# Step-to-TalkV2.net
KiCad netlist of a schematic drawn in EAGLE
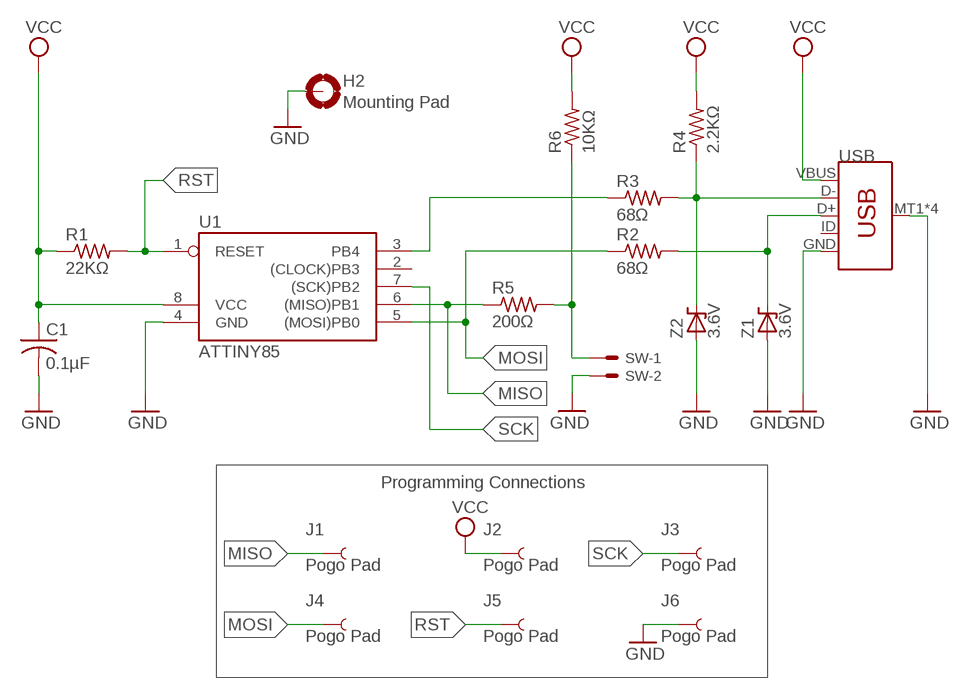
[diagram p0: schematic, sheet 1]

(export (version "E")
  (design (tool "Eeschema 10.0.6"))
  (components
    (comp (ref "C1")
      (value "0.1µF")
      (footprint "eagle-import:C0603")
      (libsource (lib "eagle-import") (part "C-USC0603"))
    )
    (comp (ref "H2")
      (value "Mounting Pad")
      (footprint "eagle-import:4,3-PAD")
      (libsource (lib "eagle-import") (part "MOUNT-PAD-ROUND4.3"))
    )
    (comp (ref "J1")
      (value "Pogo Pad")
      (footprint "eagle-import:PAD.03X.03")
      (libsource (lib "eagle-import") (part "TEST-POINT3"))
    )
    (comp (ref "J2")
      (value "Pogo Pad")
      (footprint "eagle-import:PAD.03X.03")
      (libsource (lib "eagle-import") (part "TEST-POINT3"))
    )
    (comp (ref "J3")
      (value "Pogo Pad")
      (footprint "eagle-import:PAD.03X.03")
      (libsource (lib "eagle-import") (part "TEST-POINT3"))
    )
    (comp (ref "J4")
      (value "Pogo Pad")
      (footprint "eagle-import:PAD.03X.03")
      (libsource (lib "eagle-import") (part "TEST-POINT3"))
    )
    (comp (ref "J5")
      (value "Pogo Pad")
      (footprint "eagle-import:PAD.03X.03")
      (libsource (lib "eagle-import") (part "TEST-POINT3"))
    )
    (comp (ref "J6")
      (value "Pogo Pad")
      (footprint "eagle-import:PAD.03X.03")
      (libsource (lib "eagle-import") (part "TEST-POINT3"))
    )
    (comp (ref "R1")
      (value "22KΩ")
      (footprint "eagle-import:R0603")
      (libsource (lib "eagle-import") (part "R-US_R0603"))
    )
    (comp (ref "R2")
      (value "68Ω")
      (footprint "eagle-import:R0603")
      (libsource (lib "eagle-import") (part "R-US_R0603"))
    )
    (comp (ref "R3")
      (value "68Ω")
      (footprint "eagle-import:R0603")
      (libsource (lib "eagle-import") (part "R-US_R0603"))
    )
    (comp (ref "R4")
      (value "2.2KΩ")
      (footprint "eagle-import:R0603")
      (libsource (lib "eagle-import") (part "R-US_R0603"))
    )
    (comp (ref "R5")
      (value "200Ω")
      (footprint "eagle-import:R0603")
      (libsource (lib "eagle-import") (part "R-US_R0603"))
    )
    (comp (ref "R6")
      (value "10KΩ")
      (footprint "eagle-import:R0603")
      (libsource (lib "eagle-import") (part "R-US_R0603"))
    )
    (comp (ref "SW")
      (value "87438-02")
      (footprint "eagle-import:87438-02")
      (libsource (lib "eagle-import") (part "87438-02"))
    )
    (comp (ref "U1")
      (value "ATTINY85")
      (footprint "eagle-import:SOIC8")
      (libsource (lib "eagle-import") (part "TINY22S"))
    )
    (comp (ref "USB")
      (value "USB_MICRO-B_SMT")
      (footprint "eagle-import:USB-MICROB")
      (libsource (lib "eagle-import") (part "USB_MICRO-B_SMT"))
    )
    (comp (ref "Z1")
      (value "3.6V")
      (footprint "eagle-import:SOD523-ENLARGED")
      (libsource (lib "eagle-import") (part "BZT52C3V6TENLARGED"))
    )
    (comp (ref "Z2")
      (value "3.6V")
      (footprint "eagle-import:SOD523-ENLARGED")
      (libsource (lib "eagle-import") (part "BZT52C3V6TENLARGED"))
    )
  )
  (nets
    (net (code "1") (name "GND") (class "Default")
      (node (ref "C1") (pin "2") (pinfunction "2_2") (pintype "passive"))
      (node (ref "H2") (pin "B4,3") (pinfunction "MOUNT_B4,3") (pintype "passive"))
      (node (ref "J6") (pin "P$1") (pinfunction "1_P$1") (pintype "bidirectional"))
      (node (ref "SW") (pin "2") (pinfunction "S_2") (pintype "passive"))
      (node (ref "U1") (pin "4") (pinfunction "GND_4") (pintype "power_in"))
      (node (ref "USB") (pin "GND") (pinfunction "GND_GND") (pintype "power_in"))
      (node (ref "USB") (pin "MT1") (pinfunction "SHIELD_MT1") (pintype "bidirectional"))
      (node (ref "USB") (pin "MT2") (pinfunction "SHIELD_MT2") (pintype "bidirectional"))
      (node (ref "USB") (pin "P$1") (pinfunction "SHIELD_P$1") (pintype "bidirectional"))
      (node (ref "USB") (pin "P$2") (pinfunction "SHIELD_P$2") (pintype "bidirectional"))
      (node (ref "Z1") (pin "2") (pinfunction "A_2") (pintype "passive"))
      (node (ref "Z2") (pin "2") (pinfunction "A_2") (pintype "passive"))
    )
    (net (code "2") (name "MISO") (class "Default")
      (node (ref "J1") (pin "P$1") (pinfunction "1_P$1") (pintype "bidirectional"))
      (node (ref "R5") (pin "1") (pinfunction "1_1") (pintype "passive"))
      (node (ref "U1") (pin "6") (pinfunction "(MISO)PB1_6") (pintype "bidirectional"))
    )
    (net (code "3") (name "MOSI") (class "Default")
      (node (ref "J4") (pin "P$1") (pinfunction "1_P$1") (pintype "bidirectional"))
      (node (ref "R2") (pin "1") (pinfunction "1_1") (pintype "passive"))
      (node (ref "U1") (pin "5") (pinfunction "(MOSI)PB0_5") (pintype "bidirectional"))
    )
    (net (code "4") (name "Net-(SWA-S)") (class "Default")
      (node (ref "R5") (pin "2") (pinfunction "2_2") (pintype "passive"))
      (node (ref "R6") (pin "1") (pinfunction "1_1") (pintype "passive"))
      (node (ref "SW") (pin "1") (pinfunction "S_1") (pintype "passive"))
    )
    (net (code "5") (name "Net-(U1-PB4)") (class "Default")
      (node (ref "R3") (pin "1") (pinfunction "1_1") (pintype "passive"))
      (node (ref "U1") (pin "3") (pinfunction "PB4_3") (pintype "bidirectional"))
    )
    (net (code "6") (name "Net-(Z1-K)") (class "Default")
      (node (ref "R2") (pin "2") (pinfunction "2_2") (pintype "passive"))
      (node (ref "USB") (pin "D+") (pinfunction "D+_D+") (pintype "bidirectional"))
      (node (ref "Z1") (pin "1") (pinfunction "K_1") (pintype "passive"))
    )
    (net (code "7") (name "Net-(Z2-K)") (class "Default")
      (node (ref "R3") (pin "2") (pinfunction "2_2") (pintype "passive"))
      (node (ref "R4") (pin "1") (pinfunction "1_1") (pintype "passive"))
      (node (ref "USB") (pin "D-") (pinfunction "D-_D-") (pintype "bidirectional"))
      (node (ref "Z2") (pin "1") (pinfunction "K_1") (pintype "passive"))
    )
    (net (code "8") (name "RST") (class "Default")
      (node (ref "J5") (pin "P$1") (pinfunction "1_P$1") (pintype "bidirectional"))
      (node (ref "R1") (pin "2") (pinfunction "2_2") (pintype "passive"))
      (node (ref "U1") (pin "1") (pinfunction "RESET_1") (pintype "input"))
    )
    (net (code "9") (name "SCK") (class "Default")
      (node (ref "J3") (pin "P$1") (pinfunction "1_P$1") (pintype "bidirectional"))
      (node (ref "U1") (pin "7") (pinfunction "(SCK)PB2_7") (pintype "bidirectional"))
    )
    (net (code "10") (name "VCC") (class "Default")
      (node (ref "C1") (pin "1") (pinfunction "1_1") (pintype "passive"))
      (node (ref "J2") (pin "P$1") (pinfunction "1_P$1") (pintype "bidirectional"))
      (node (ref "R1") (pin "1") (pinfunction "1_1") (pintype "passive"))
      (node (ref "R4") (pin "2") (pinfunction "2_2") (pintype "passive"))
      (node (ref "R6") (pin "2") (pinfunction "2_2") (pintype "passive"))
      (node (ref "U1") (pin "8") (pinfunction "VCC_8") (pintype "power_in"))
      (node (ref "USB") (pin "VBUS") (pinfunction "VBUS_VBUS") (pintype "power_in"))
    )
    (net (code "11") (name "unconnected-(U1-(CLOCK)PB3-Pad2)") (class "Default")
      (node (ref "U1") (pin "2") (pinfunction "(CLOCK)PB3_2") (pintype "bidirectional"))
    )
    (net (code "12") (name "unconnected-(USB-PadID)") (class "Default")
      (node (ref "USB") (pin "ID") (pinfunction "ID_ID") (pintype "bidirectional"))
    )
  )
)
